# USB-Weather.net
KiCad netlist of a schematic drawn in EAGLE
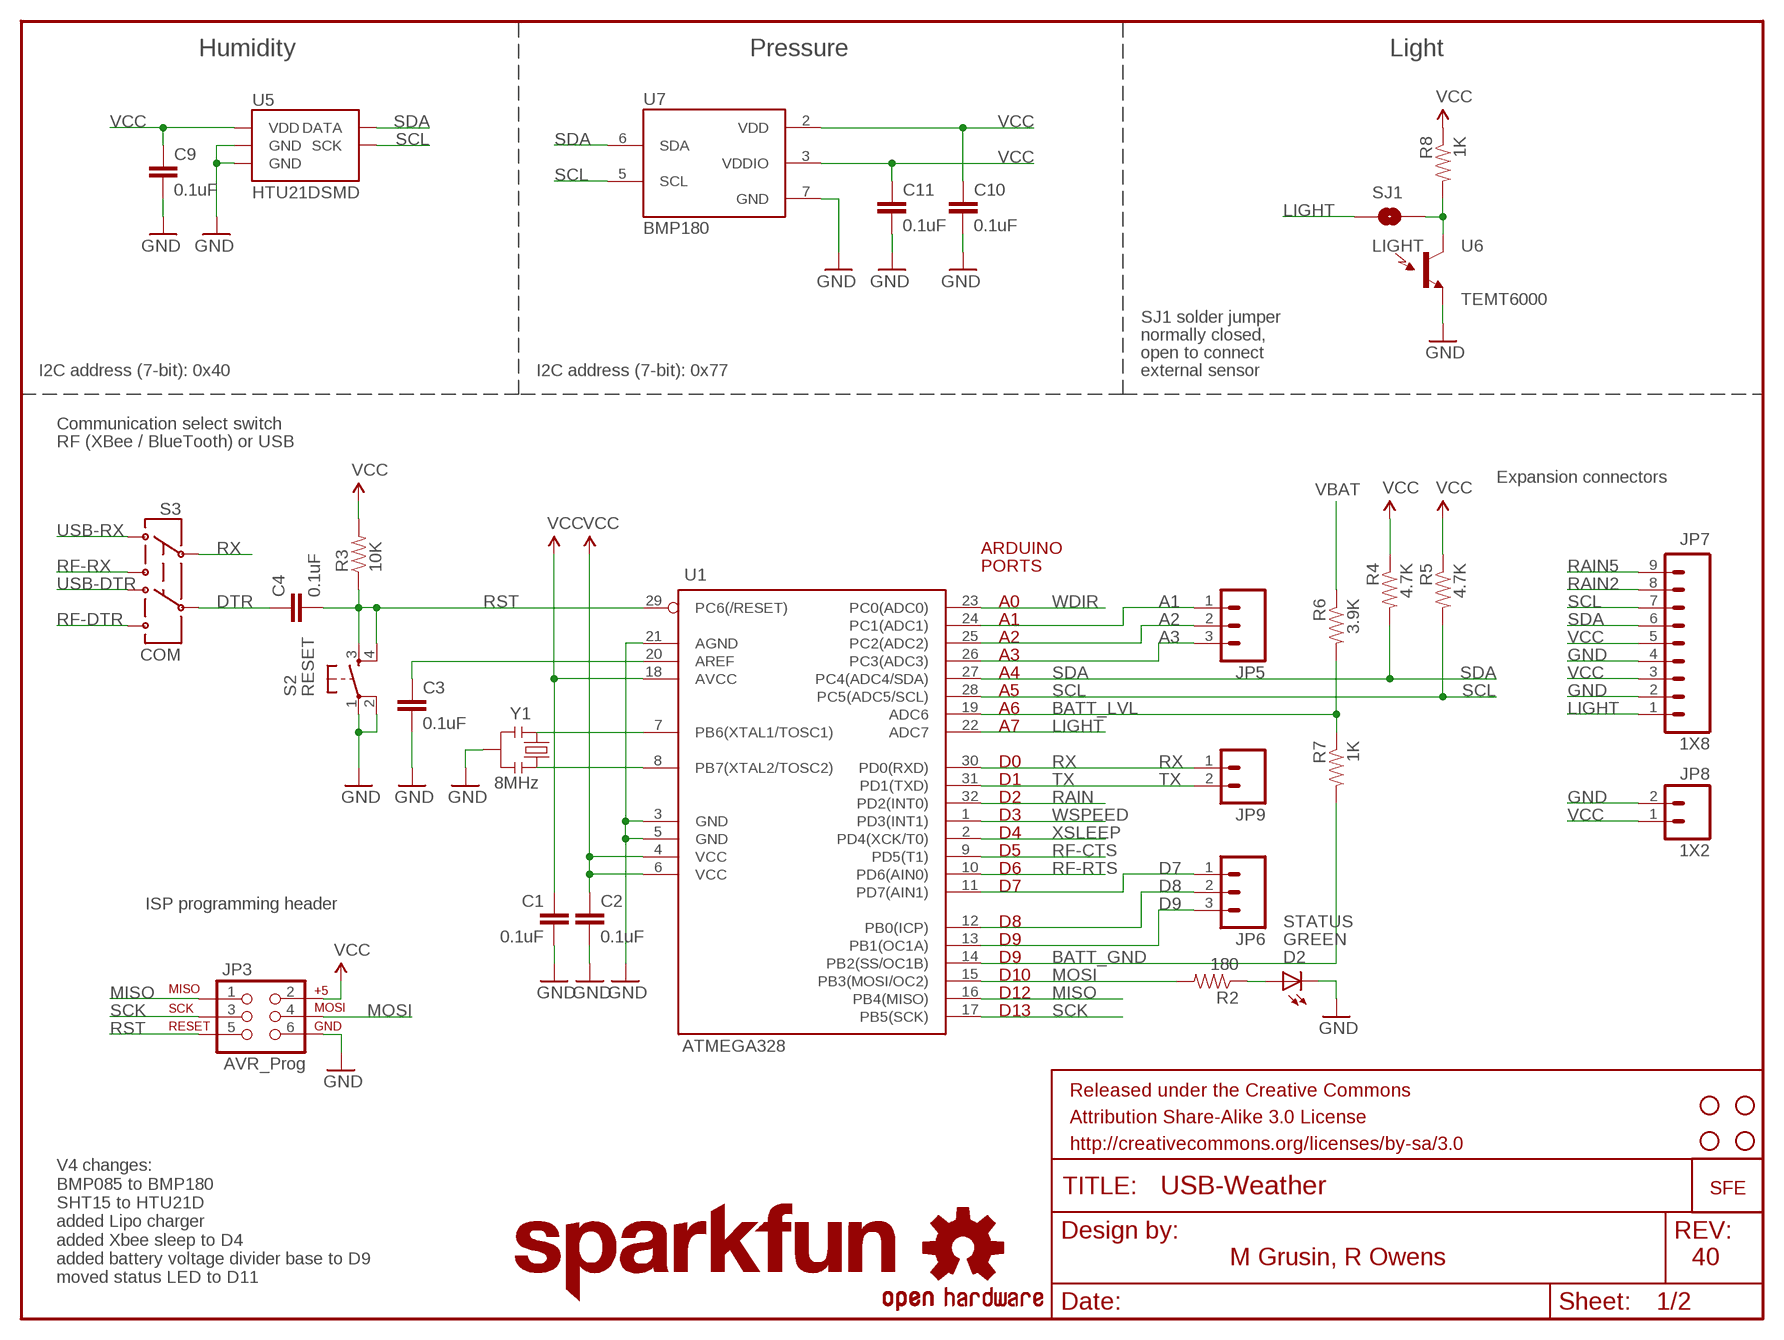
[diagram p0: schematic, sheet 1]
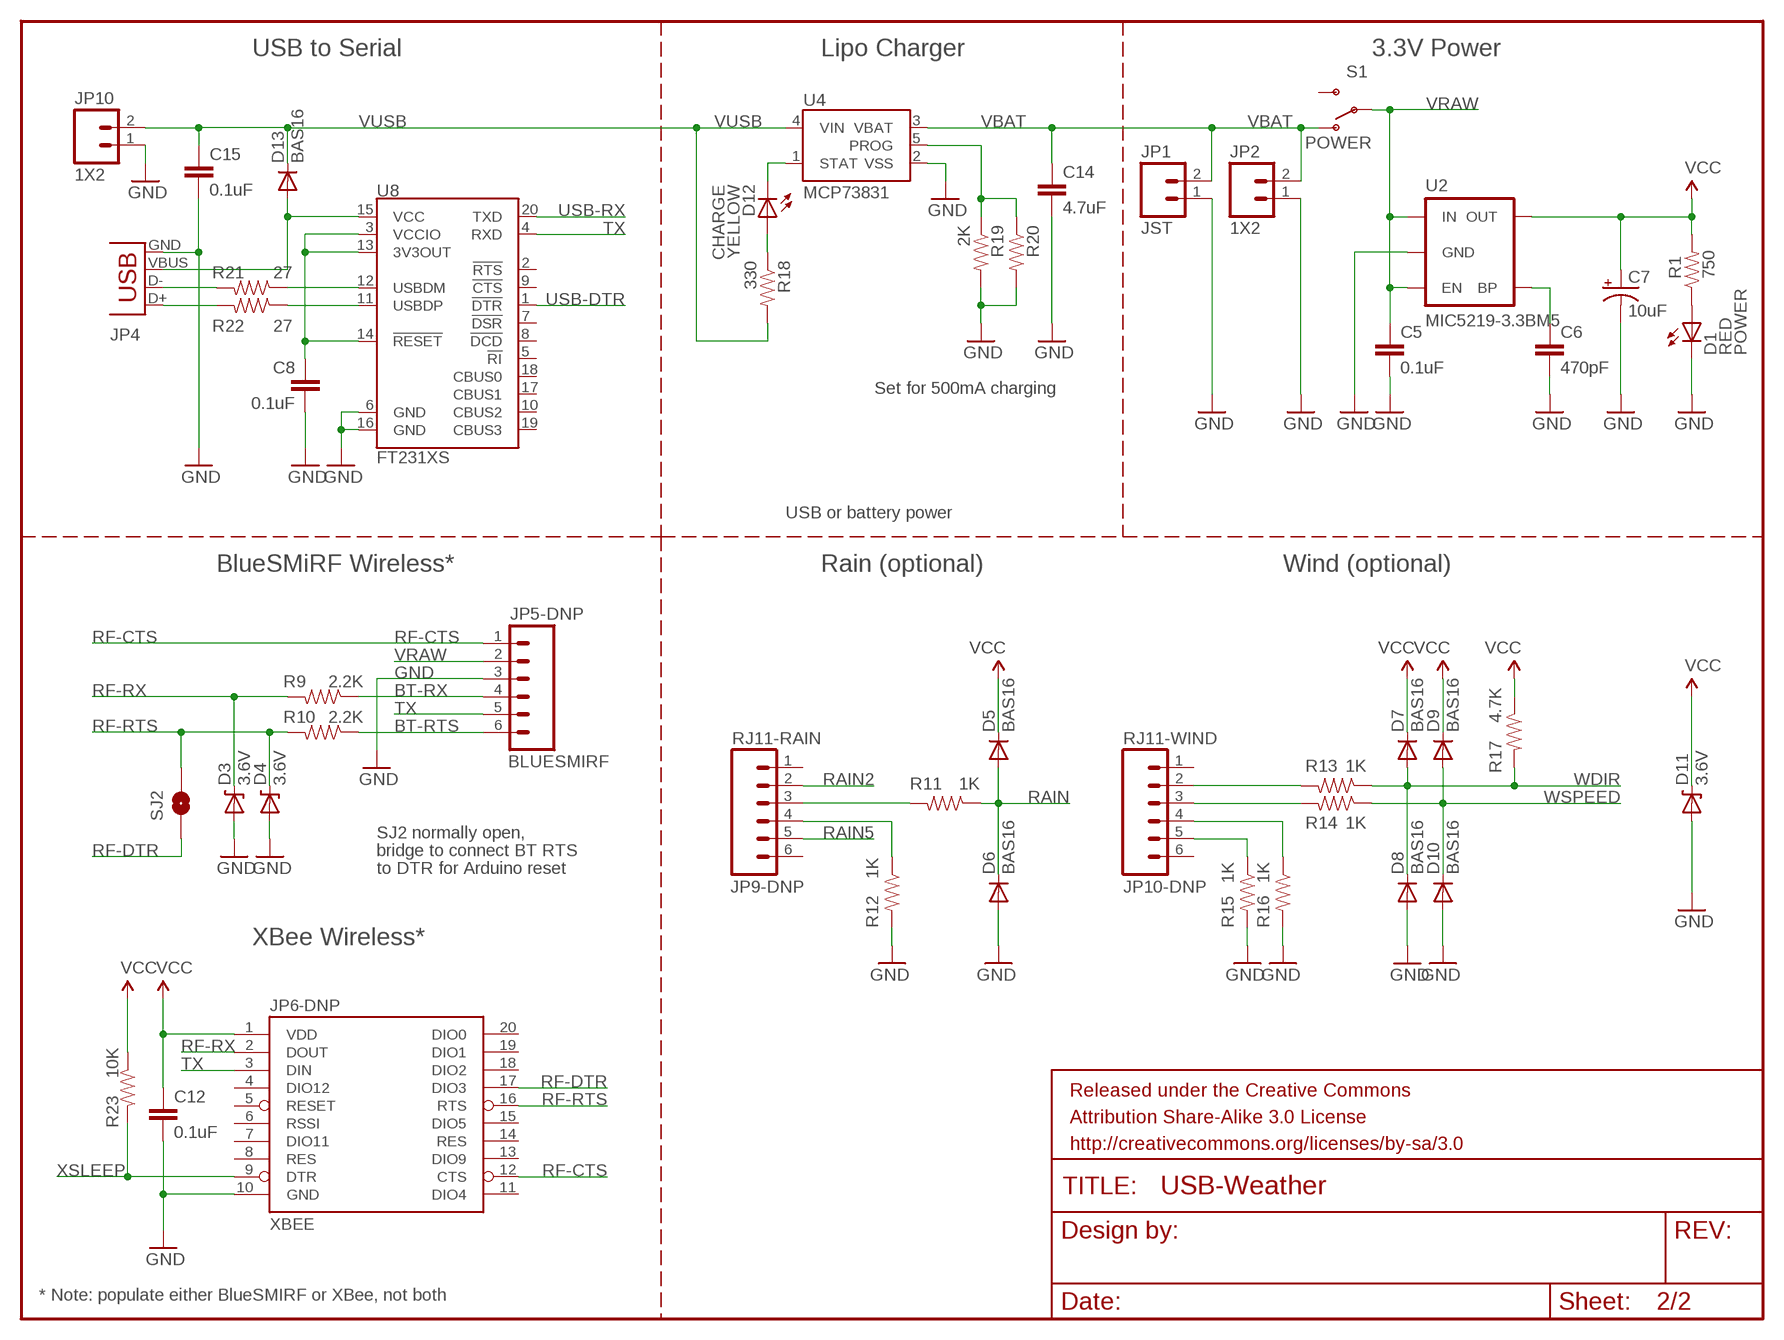
[diagram p1: schematic, sheet 2]

(export (version "E")
  (design (tool "Eeschema 10.0.6"))
  (components
    (comp (ref "C5")
      (value "0.1uF")
      (footprint "eagle-import:0603-CAP")
      (libsource (lib "eagle-import") (part "CAP0603-CAP"))
    )
    (comp (ref "C6")
      (value "470pF")
      (footprint "eagle-import:0603-CAP")
      (libsource (lib "eagle-import") (part "CAP0603-CAP"))
    )
    (comp (ref "C7")
      (value "10uF")
      (footprint "eagle-import:EIA3216")
      (libsource (lib "eagle-import") (part "CAP_POL1206"))
    )
    (comp (ref "C8")
      (value "0.1uF")
      (footprint "eagle-import:0603-CAP")
      (libsource (lib "eagle-import") (part "CAP0603-CAP"))
    )
    (comp (ref "C12")
      (value "0.1uF")
      (footprint "eagle-import:0603-CAP")
      (libsource (lib "eagle-import") (part "CAP0603-CAP"))
    )
    (comp (ref "C14")
      (value "4.7uF")
      (footprint "eagle-import:0603-CAP")
      (libsource (lib "eagle-import") (part "CAP0603-CAP"))
    )
    (comp (ref "C15")
      (value "0.1uF")
      (footprint "eagle-import:0603-CAP")
      (libsource (lib "eagle-import") (part "CAP0603-CAP"))
    )
    (comp (ref "D1")
      (value "RED")
      (footprint "eagle-import:LED-0603")
      (libsource (lib "eagle-import") (part "LED0603"))
    )
    (comp (ref "D3")
      (value "3.6V")
      (footprint "eagle-import:SOD-323")
      (libsource (lib "eagle-import") (part "DIODE-ZENER-BZT52"))
    )
    (comp (ref "D4")
      (value "3.6V")
      (footprint "eagle-import:SOD-323")
      (libsource (lib "eagle-import") (part "DIODE-ZENER-BZT52"))
    )
    (comp (ref "D5")
      (value "BAS16")
      (footprint "eagle-import:SOD-323")
      (libsource (lib "eagle-import") (part "DIODESOD"))
    )
    (comp (ref "D6")
      (value "BAS16")
      (footprint "eagle-import:SOD-323")
      (libsource (lib "eagle-import") (part "DIODESOD"))
    )
    (comp (ref "D7")
      (value "BAS16")
      (footprint "eagle-import:SOD-323")
      (libsource (lib "eagle-import") (part "DIODESOD"))
    )
    (comp (ref "D8")
      (value "BAS16")
      (footprint "eagle-import:SOD-323")
      (libsource (lib "eagle-import") (part "DIODESOD"))
    )
    (comp (ref "D9")
      (value "BAS16")
      (footprint "eagle-import:SOD-323")
      (libsource (lib "eagle-import") (part "DIODESOD"))
    )
    (comp (ref "D10")
      (value "BAS16")
      (footprint "eagle-import:SOD-323")
      (libsource (lib "eagle-import") (part "DIODESOD"))
    )
    (comp (ref "D11")
      (value "3.6V")
      (footprint "eagle-import:SOD-323")
      (libsource (lib "eagle-import") (part "DIODE-ZENER-BZT52"))
    )
    (comp (ref "D12")
      (value "YELLOW")
      (footprint "eagle-import:LED-0603")
      (libsource (lib "eagle-import") (part "LED0603"))
    )
    (comp (ref "D13")
      (value "BAS16")
      (footprint "eagle-import:SOD-323")
      (libsource (lib "eagle-import") (part "DIODESOD"))
    )
    (comp (ref "FRAME1")
      (value "FRAME-LETTER")
      (footprint "eagle-import:CREATIVE_COMMONS")
      (libsource (lib "eagle-import") (part "FRAME-LETTER"))
    )
    (comp (ref "JP1")
      (value "JST")
      (footprint "eagle-import:JST-2-SMD")
      (libsource (lib "eagle-import") (part "M02-JST-2MM-SMT"))
    )
    (comp (ref "JP2")
      (value "1X2")
      (footprint "eagle-import:1X02_NO_SILK")
      (libsource (lib "eagle-import") (part "M021X02_NO_SILK"))
    )
    (comp (ref "JP4")
      (value "USBSMD")
      (footprint "eagle-import:USB-MINIB")
      (libsource (lib "eagle-import") (part "USBSMD"))
    )
    (comp (ref "JP5-DNP")
      (value "BLUESMIRF")
      (footprint "eagle-import:1X06")
      (libsource (lib "eagle-import") (part "M06SIP"))
    )
    (comp (ref "JP6-DNP")
      (value "XBEE")
      (footprint "eagle-import:XBEE-1")
      (libsource (lib "eagle-import") (part "XBEE-1B1"))
    )
    (comp (ref "JP9-DNP")
      (value "RJ11-RAIN")
      (footprint "eagle-import:RJ11-6")
      (libsource (lib "eagle-import") (part "RJ11-6PTH"))
    )
    (comp (ref "JP10")
      (value "1X2")
      (footprint "eagle-import:1X02_NO_SILK")
      (libsource (lib "eagle-import") (part "M021X02_NO_SILK"))
    )
    (comp (ref "JP10-DNP")
      (value "RJ11-WIND")
      (footprint "eagle-import:RJ11-6")
      (libsource (lib "eagle-import") (part "RJ11-6PTH"))
    )
    (comp (ref "R1")
      (value "750")
      (footprint "eagle-import:0603-RES")
      (libsource (lib "eagle-import") (part "RESISTOR0603-RES"))
    )
    (comp (ref "R9")
      (value "2.2K")
      (footprint "eagle-import:0603-RES")
      (libsource (lib "eagle-import") (part "RESISTOR0603-RES"))
    )
    (comp (ref "R10")
      (value "2.2K")
      (footprint "eagle-import:0603-RES")
      (libsource (lib "eagle-import") (part "RESISTOR0603-RES"))
    )
    (comp (ref "R11")
      (value "1K")
      (footprint "eagle-import:0603-RES")
      (libsource (lib "eagle-import") (part "RESISTOR0603-RES"))
    )
    (comp (ref "R12")
      (value "1K")
      (footprint "eagle-import:0603-RES")
      (libsource (lib "eagle-import") (part "RESISTOR0603-RES"))
    )
    (comp (ref "R13")
      (value "1K")
      (footprint "eagle-import:0603-RES")
      (libsource (lib "eagle-import") (part "RESISTOR0603-RES"))
    )
    (comp (ref "R14")
      (value "1K")
      (footprint "eagle-import:0603-RES")
      (libsource (lib "eagle-import") (part "RESISTOR0603-RES"))
    )
    (comp (ref "R15")
      (value "1K")
      (footprint "eagle-import:0603-RES")
      (libsource (lib "eagle-import") (part "RESISTOR0603-RES"))
    )
    (comp (ref "R16")
      (value "1K")
      (footprint "eagle-import:0603-RES")
      (libsource (lib "eagle-import") (part "RESISTOR0603-RES"))
    )
    (comp (ref "R17")
      (value "4.7K")
      (footprint "eagle-import:0603-RES")
      (libsource (lib "eagle-import") (part "RESISTOR0603-RES"))
    )
    (comp (ref "R18")
      (value "330")
      (footprint "eagle-import:0603-RES")
      (libsource (lib "eagle-import") (part "RESISTOR0603-RES"))
    )
    (comp (ref "R19")
      (value "2K")
      (footprint "eagle-import:0603-RES")
      (libsource (lib "eagle-import") (part "RESISTOR0603-RES"))
    )
    (comp (ref "R20")
      (value "RESISTORPTH-1/6W")
      (footprint "eagle-import:1_6W-RES")
      (libsource (lib "eagle-import") (part "RESISTORPTH-1/6W"))
    )
    (comp (ref "R21")
      (value "27")
      (footprint "eagle-import:0603-RES")
      (libsource (lib "eagle-import") (part "RESISTOR0603-RES"))
    )
    (comp (ref "R22")
      (value "27")
      (footprint "eagle-import:0603-RES")
      (libsource (lib "eagle-import") (part "RESISTOR0603-RES"))
    )
    (comp (ref "R23")
      (value "10K")
      (footprint "eagle-import:0603-RES")
      (libsource (lib "eagle-import") (part "RESISTOR0603-RES"))
    )
    (comp (ref "S1")
      (value "POWER")
      (footprint "eagle-import:AYZ0202")
      (libsource (lib "eagle-import") (part "SWITCH-SPSTSMD"))
    )
    (comp (ref "SJ2")
      (value "SOLDERJUMPERNO")
      (footprint "eagle-import:SJ_2S-NO")
      (libsource (lib "eagle-import") (part "SOLDERJUMPERNO"))
    )
    (comp (ref "U2")
      (value "MIC5219-3.3BM5")
      (footprint "eagle-import:SOT23-5")
      (libsource (lib "eagle-import") (part "V_REG_LDOSMD"))
    )
    (comp (ref "U4")
      (value "MCP73831")
      (footprint "eagle-import:SOT23-5")
      (libsource (lib "eagle-import") (part "MCP73831"))
    )
    (comp (ref "U8")
      (value "FT231XS")
      (footprint "eagle-import:SSOP20_L")
      (libsource (lib "eagle-import") (part "FT231XS"))
    )
    (comp (ref "C1")
      (value "0.1uF")
      (footprint "eagle-import:0603-CAP")
      (libsource (lib "eagle-import") (part "CAP0603-CAP"))
    )
    (comp (ref "C2")
      (value "0.1uF")
      (footprint "eagle-import:0603-CAP")
      (libsource (lib "eagle-import") (part "CAP0603-CAP"))
    )
    (comp (ref "C3")
      (value "0.1uF")
      (footprint "eagle-import:0603-CAP")
      (libsource (lib "eagle-import") (part "CAP0603-CAP"))
    )
    (comp (ref "C4")
      (value "0.1uF")
      (footprint "eagle-import:0603-CAP")
      (libsource (lib "eagle-import") (part "CAP0603-CAP"))
    )
    (comp (ref "C9")
      (value "0.1uF")
      (footprint "eagle-import:0603-CAP")
      (libsource (lib "eagle-import") (part "CAP0603-CAP"))
    )
    (comp (ref "C10")
      (value "0.1uF")
      (footprint "eagle-import:0603-CAP")
      (libsource (lib "eagle-import") (part "CAP0603-CAP"))
    )
    (comp (ref "C11")
      (value "0.1uF")
      (footprint "eagle-import:0603-CAP")
      (libsource (lib "eagle-import") (part "CAP0603-CAP"))
    )
    (comp (ref "D2")
      (value "GREEN")
      (footprint "eagle-import:LED-0603")
      (libsource (lib "eagle-import") (part "LED0603"))
    )
    (comp (ref "FRAME3")
      (value "FRAME-LETTER")
      (footprint "eagle-import:CREATIVE_COMMONS")
      (libsource (lib "eagle-import") (part "FRAME-LETTER"))
    )
    (comp (ref "JP3")
      (value "AVR_Prog")
      (footprint "eagle-import:2X3")
      (libsource (lib "eagle-import") (part "AVR_SPI_PRG_6PTH"))
    )
    (comp (ref "JP5")
      (value "M03_ROUND_ONLY_NO_SILK")
      (footprint "eagle-import:1X03_ROUND_ONLY_NO_SILK")
      (libsource (lib "eagle-import") (part "M03_ROUND_ONLY_NO_SILK"))
    )
    (comp (ref "JP6")
      (value "M03_ROUND_ONLY_NO_SILK")
      (footprint "eagle-import:1X03_ROUND_ONLY_NO_SILK")
      (libsource (lib "eagle-import") (part "M03_ROUND_ONLY_NO_SILK"))
    )
    (comp (ref "JP7")
      (value "1X8")
      (footprint "eagle-import:1X09")
      (libsource (lib "eagle-import") (part "M09"))
    )
    (comp (ref "JP8")
      (value "1X2")
      (footprint "eagle-import:1X02_NO_SILK")
      (libsource (lib "eagle-import") (part "mike-temp_M021X02_NO_SILK"))
    )
    (comp (ref "JP9")
      (value "M021X02_NO_SILK")
      (footprint "eagle-import:1X02_NO_SILK")
      (libsource (lib "eagle-import") (part "mike-temp_M021X02_NO_SILK"))
    )
    (comp (ref "LOGO1")
      (value "LOGO-SFENEW")
      (footprint "eagle-import:SFE-NEW-WEBLOGO")
      (libsource (lib "eagle-import") (part "LOGO-SFENEW"))
    )
    (comp (ref "LOGO2")
      (value "OSHW-LOGOS")
      (footprint "eagle-import:OSHW-LOGO-S")
      (libsource (lib "eagle-import") (part "OSHW-LOGOS"))
    )
    (comp (ref "LOGO3")
      (value "SFE_LOGO_NAME.1_INCH")
      (footprint "eagle-import:SFE_LOGO_NAME_.1")
      (libsource (lib "eagle-import") (part "SFE_LOGO_NAME.1_INCH"))
    )
    (comp (ref "R2")
      (value "180")
      (footprint "eagle-import:0603-RES")
      (libsource (lib "eagle-import") (part "RESISTOR0603-RES"))
    )
    (comp (ref "R3")
      (value "10K")
      (footprint "eagle-import:0603-RES")
      (libsource (lib "eagle-import") (part "RESISTOR0603-RES"))
    )
    (comp (ref "R4")
      (value "4.7K")
      (footprint "eagle-import:0603-RES")
      (libsource (lib "eagle-import") (part "RESISTOR0603-RES"))
    )
    (comp (ref "R5")
      (value "4.7K")
      (footprint "eagle-import:0603-RES")
      (libsource (lib "eagle-import") (part "RESISTOR0603-RES"))
    )
    (comp (ref "R6")
      (value "3.9K")
      (footprint "eagle-import:0603-RES")
      (libsource (lib "eagle-import") (part "RESISTOR0603-RES"))
    )
    (comp (ref "R7")
      (value "1K")
      (footprint "eagle-import:0603-RES")
      (libsource (lib "eagle-import") (part "RESISTOR0603-RES"))
    )
    (comp (ref "R8")
      (value "1K")
      (footprint "eagle-import:0603-RES")
      (libsource (lib "eagle-import") (part "RESISTOR0603-RES"))
    )
    (comp (ref "S2")
      (value "RESET")
      (footprint "eagle-import:TACTILE_SWITCH_SMD")
      (libsource (lib "eagle-import") (part "TAC_SWITCHSMD"))
    )
    (comp (ref "S3")
      (value "COM")
      (footprint "eagle-import:AYZ0202")
      (libsource (lib "eagle-import") (part "SWITCH-DPDTSMD"))
    )
    (comp (ref "SJ1")
      (value "LIGHT")
      (footprint "eagle-import:SJ_2S")
      (libsource (lib "eagle-import") (part "SOLDERJUMPERNC"))
    )
    (comp (ref "U$2")
      (value "STAND-OFF")
      (footprint "eagle-import:STAND-OFF")
      (libsource (lib "eagle-import") (part "STAND-OFF"))
    )
    (comp (ref "U$3")
      (value "STAND-OFF")
      (footprint "eagle-import:STAND-OFF")
      (libsource (lib "eagle-import") (part "STAND-OFF"))
    )
    (comp (ref "U$4")
      (value "STAND-OFF")
      (footprint "eagle-import:STAND-OFF")
      (libsource (lib "eagle-import") (part "STAND-OFF"))
    )
    (comp (ref "U$5")
      (value "STAND-OFF")
      (footprint "eagle-import:STAND-OFF")
      (libsource (lib "eagle-import") (part "STAND-OFF"))
    )
    (comp (ref "U1")
      (value "ATMEGA328")
      (footprint "eagle-import:TQFP32-08")
      (libsource (lib "eagle-import") (part "AVR-MEGA8-AI"))
    )
    (comp (ref "U5")
      (value "HTU21DSMD")
      (footprint "eagle-import:HTU21D")
      (libsource (lib "eagle-import") (part "HTU21DSMD"))
    )
    (comp (ref "U6")
      (value "TEMT6000")
      (footprint "eagle-import:TEMT6000-SEN")
      (libsource (lib "eagle-import") (part "TEMT6000"))
    )
    (comp (ref "U7")
      (value "BMP180")
      (footprint "eagle-import:BMP180")
      (libsource (lib "eagle-import") (part "BMP180"))
    )
    (comp (ref "Y1")
      (value "8MHz")
      (footprint "eagle-import:RESONATOR-SMD")
      (libsource (lib "eagle-import") (part "RESONATORSMD"))
    )
  )
  (nets
    (net (code "1") (name "A1") (class "Default")
      (node (ref "JP5") (pin "1") (pinfunction "1_1") (pintype "passive"))
      (node (ref "U1") (pin "24") (pinfunction "PC1(ADC1)_24") (pintype "bidirectional"))
    )
    (net (code "2") (name "A2") (class "Default")
      (node (ref "JP5") (pin "2") (pinfunction "2_2") (pintype "passive"))
      (node (ref "U1") (pin "25") (pinfunction "PC2(ADC2)_25") (pintype "bidirectional"))
    )
    (net (code "3") (name "A3") (class "Default")
      (node (ref "JP5") (pin "3") (pinfunction "3_3") (pintype "passive"))
      (node (ref "U1") (pin "26") (pinfunction "PC3(ADC3)_26") (pintype "bidirectional"))
    )
    (net (code "4") (name "BATT_GND") (class "Default")
      (node (ref "R7") (pin "2") (pinfunction "2_2") (pintype "passive"))
      (node (ref "U1") (pin "14") (pinfunction "PB2(SS/OC1B)_14") (pintype "bidirectional"))
    )
    (net (code "5") (name "BATT_LVL") (class "Default")
      (node (ref "R6") (pin "2") (pinfunction "2_2") (pintype "passive"))
      (node (ref "R7") (pin "1") (pinfunction "1_1") (pintype "passive"))
      (node (ref "U1") (pin "19") (pinfunction "ADC6_19") (pintype "bidirectional"))
    )
    (net (code "6") (name "BT-RTS") (class "Default")
      (node (ref "JP5-DNP") (pin "6") (pinfunction "6_6") (pintype "passive"))
      (node (ref "R10") (pin "1") (pinfunction "1_1") (pintype "passive"))
    )
    (net (code "7") (name "BT-RX") (class "Default")
      (node (ref "JP5-DNP") (pin "4") (pinfunction "4_4") (pintype "passive"))
      (node (ref "R9") (pin "1") (pinfunction "1_1") (pintype "passive"))
    )
    (net (code "8") (name "D7") (class "Default")
      (node (ref "JP6") (pin "1") (pinfunction "1_1") (pintype "passive"))
      (node (ref "U1") (pin "11") (pinfunction "PD7(AIN1)_11") (pintype "bidirectional"))
    )
    (net (code "9") (name "D8") (class "Default")
      (node (ref "JP6") (pin "2") (pinfunction "2_2") (pintype "passive"))
      (node (ref "U1") (pin "12") (pinfunction "PB0(ICP)_12") (pintype "bidirectional"))
    )
    (net (code "10") (name "D9") (class "Default")
      (node (ref "JP6") (pin "3") (pinfunction "3_3") (pintype "passive"))
      (node (ref "U1") (pin "13") (pinfunction "PB1(OC1A)_13") (pintype "bidirectional"))
    )
    (net (code "11") (name "DTR") (class "Default")
      (node (ref "C4") (pin "1") (pinfunction "1_1") (pintype "passive"))
      (node (ref "S3") (pin "5") (pinfunction "5_5") (pintype "bidirectional"))
    )
    (net (code "12") (name "GND") (class "Default")
      (node (ref "C1") (pin "2") (pinfunction "2_2") (pintype "passive"))
      (node (ref "C10") (pin "2") (pinfunction "2_2") (pintype "passive"))
      (node (ref "C11") (pin "2") (pinfunction "2_2") (pintype "passive"))
      (node (ref "C12") (pin "2") (pinfunction "2_2") (pintype "passive"))
      (node (ref "C14") (pin "2") (pinfunction "2_2") (pintype "passive"))
      (node (ref "C15") (pin "2") (pinfunction "2_2") (pintype "passive"))
      (node (ref "C2") (pin "2") (pinfunction "2_2") (pintype "passive"))
      (node (ref "C3") (pin "2") (pinfunction "2_2") (pintype "passive"))
      (node (ref "C5") (pin "2") (pinfunction "2_2") (pintype "passive"))
      (node (ref "C6") (pin "2") (pinfunction "2_2") (pintype "passive"))
      (node (ref "C7") (pin "C") (pinfunction "-_C") (pintype "passive"))
      (node (ref "C8") (pin "2") (pinfunction "2_2") (pintype "passive"))
      (node (ref "C9") (pin "2") (pinfunction "2_2") (pintype "passive"))
      (node (ref "D1") (pin "C") (pinfunction "C_C") (pintype "passive"))
      (node (ref "D10") (pin "2") (pinfunction "A_2") (pintype "passive"))
      (node (ref "D11") (pin "2") (pinfunction "A_2") (pintype "passive"))
      (node (ref "D2") (pin "C") (pinfunction "C_C") (pintype "passive"))
      (node (ref "D3") (pin "2") (pinfunction "A_2") (pintype "passive"))
      (node (ref "D4") (pin "2") (pinfunction "A_2") (pintype "passive"))
      (node (ref "D6") (pin "2") (pinfunction "A_2") (pintype "passive"))
      (node (ref "D8") (pin "2") (pinfunction "A_2") (pintype "passive"))
      (node (ref "JP1") (pin "1") (pinfunction "1_1") (pintype "passive"))
      (node (ref "JP10") (pin "1") (pinfunction "1_1") (pintype "passive"))
      (node (ref "JP2") (pin "1") (pinfunction "1_1") (pintype "passive"))
      (node (ref "JP3") (pin "6") (pinfunction "6_6") (pintype "passive"))
      (node (ref "JP4") (pin "GND") (pinfunction "GND_GND") (pintype "bidirectional"))
      (node (ref "JP5-DNP") (pin "3") (pinfunction "3_3") (pintype "passive"))
      (node (ref "JP6-DNP") (pin "10") (pinfunction "GND_10") (pintype "power_in"))
      (node (ref "JP7") (pin "2") (pinfunction "2_2") (pintype "passive"))
      (node (ref "JP7") (pin "4") (pinfunction "4_4") (pintype "passive"))
      (node (ref "JP8") (pin "2") (pinfunction "2_2") (pintype "passive"))
      (node (ref "R12") (pin "2") (pinfunction "2_2") (pintype "passive"))
      (node (ref "R15") (pin "2") (pinfunction "2_2") (pintype "passive"))
      (node (ref "R16") (pin "2") (pinfunction "2_2") (pintype "passive"))
      (node (ref "R19") (pin "2") (pinfunction "2_2") (pintype "passive"))
      (node (ref "R20") (pin "2") (pinfunction "2_2") (pintype "passive"))
      (node (ref "S2") (pin "1") (pinfunction "1_1") (pintype "passive"))
      (node (ref "S2") (pin "2") (pinfunction "2_2") (pintype "passive"))
      (node (ref "U1") (pin "21") (pinfunction "AGND_21") (pintype "bidirectional"))
      (node (ref "U1") (pin "3") (pinfunction "GND_3") (pintype "bidirectional"))
      (node (ref "U1") (pin "5") (pinfunction "GND_5") (pintype "bidirectional"))
      (node (ref "U2") (pin "2") (pinfunction "GND_2") (pintype "input"))
      (node (ref "U4") (pin "2") (pinfunction "VSS_2") (pintype "power_in"))
      (node (ref "U5") (pin "7") (pinfunction "GND_7") (pintype "power_in"))
      (node (ref "U5") (pin "GND") (pinfunction "GND_GND") (pintype "power_in"))
      (node (ref "U6") (pin "EMITTER") (pinfunction "E1_EMITTER") (pintype "passive"))
      (node (ref "U7") (pin "7") (pinfunction "GND_7") (pintype "power_in"))
      (node (ref "U8") (pin "16") (pinfunction "GND_16") (pintype "bidirectional"))
      (node (ref "U8") (pin "6") (pinfunction "GND_6") (pintype "bidirectional"))
      (node (ref "Y1") (pin "2") (pinfunction "2_2") (pintype "passive"))
    )
    (net (code "13") (name "LIGHT") (class "Default")
      (node (ref "JP7") (pin "1") (pinfunction "1_1") (pintype "passive"))
      (node (ref "SJ1") (pin "1") (pinfunction "1_1") (pintype "passive"))
      (node (ref "U1") (pin "22") (pinfunction "ADC7_22") (pintype "bidirectional"))
    )
    (net (code "14") (name "MISO") (class "Default")
      (node (ref "JP3") (pin "1") (pinfunction "1_1") (pintype "passive"))
      (node (ref "U1") (pin "16") (pinfunction "PB4(MISO)_16") (pintype "bidirectional"))
    )
    (net (code "15") (name "MOSI") (class "Default")
      (node (ref "JP3") (pin "4") (pinfunction "4_4") (pintype "passive"))
      (node (ref "R2") (pin "2") (pinfunction "2_2") (pintype "passive"))
      (node (ref "U1") (pin "15") (pinfunction "PB3(MOSI/OC2)_15") (pintype "bidirectional"))
    )
    (net (code "16") (name "Net-(D1-PadA)") (class "Default")
      (node (ref "D1") (pin "A") (pinfunction "A_A") (pintype "passive"))
      (node (ref "R1") (pin "1") (pinfunction "1_1") (pintype "passive"))
    )
    (net (code "17") (name "Net-(D2-PadA)") (class "Default")
      (node (ref "D2") (pin "A") (pinfunction "A_A") (pintype "passive"))
      (node (ref "R2") (pin "1") (pinfunction "1_1") (pintype "passive"))
    )
    (net (code "18") (name "Net-(D12-PadA)") (class "Default")
      (node (ref "D12") (pin "A") (pinfunction "A_A") (pintype "passive"))
      (node (ref "R18") (pin "1") (pinfunction "1_1") (pintype "passive"))
    )
    (net (code "19") (name "Net-(D13-A)") (class "Default")
      (node (ref "D13") (pin "2") (pinfunction "A_2") (pintype "passive"))
      (node (ref "JP4") (pin "VBUS") (pinfunction "VBUS_VBUS") (pintype "bidirectional"))
      (node (ref "U8") (pin "15") (pinfunction "VCC_15") (pintype "bidirectional"))
    )
    (net (code "20") (name "Net-(JP4-PadD+)") (class "Default")
      (node (ref "JP4") (pin "D+") (pinfunction "D+_D+") (pintype "bidirectional"))
      (node (ref "R22") (pin "2") (pinfunction "2_2") (pintype "passive"))
    )
    (net (code "21") (name "Net-(JP4-PadD-)") (class "Default")
      (node (ref "JP4") (pin "D-") (pinfunction "D-_D-") (pintype "bidirectional"))
      (node (ref "R21") (pin "2") (pinfunction "2_2") (pintype "passive"))
    )
    (net (code "22") (name "Net-(JP9-DNP-Pad3)") (class "Default")
      (node (ref "JP9-DNP") (pin "3") (pinfunction "3_3") (pintype "passive"))
      (node (ref "R11") (pin "2") (pinfunction "2_2") (pintype "passive"))
    )
    (net (code "23") (name "Net-(JP9-DNP-Pad4)") (class "Default")
      (node (ref "JP9-DNP") (pin "4") (pinfunction "4_4") (pintype "passive"))
      (node (ref "R12") (pin "1") (pinfunction "1_1") (pintype "passive"))
    )
    (net (code "24") (name "Net-(JP10-DNP-Pad2)") (class "Default")
      (node (ref "JP10-DNP") (pin "2") (pinfunction "2_2") (pintype "passive"))
      (node (ref "R13") (pin "2") (pinfunction "2_2") (pintype "passive"))
    )
    (net (code "25") (name "Net-(JP10-DNP-Pad3)") (class "Default")
      (node (ref "JP10-DNP") (pin "3") (pinfunction "3_3") (pintype "passive"))
      (node (ref "R14") (pin "2") (pinfunction "2_2") (pintype "passive"))
    )
    (net (code "26") (name "Net-(JP10-DNP-Pad4)") (class "Default")
      (node (ref "JP10-DNP") (pin "4") (pinfunction "4_4") (pintype "passive"))
      (node (ref "R16") (pin "1") (pinfunction "1_1") (pintype "passive"))
    )
    (net (code "27") (name "Net-(JP10-DNP-Pad5)") (class "Default")
      (node (ref "JP10-DNP") (pin "5") (pinfunction "5_5") (pintype "passive"))
      (node (ref "R15") (pin "1") (pinfunction "1_1") (pintype "passive"))
    )
    (net (code "28") (name "Net-(U1-AREF)") (class "Default")
      (node (ref "C3") (pin "1") (pinfunction "1_1") (pintype "passive"))
      (node (ref "U1") (pin "20") (pinfunction "AREF_20") (pintype "bidirectional"))
    )
    (net (code "29") (name "Net-(U1-PB6(XTAL1{slash}TOSC1))") (class "Default")
      (node (ref "U1") (pin "7") (pinfunction "PB6(XTAL1/TOSC1)_7") (pintype "bidirectional"))
      (node (ref "Y1") (pin "1") (pinfunction "1_1") (pintype "passive"))
    )
    (net (code "30") (name "Net-(U1-PB7(XTAL2{slash}TOSC2))") (class "Default")
      (node (ref "U1") (pin "8") (pinfunction "PB7(XTAL2/TOSC2)_8") (pintype "bidirectional"))
      (node (ref "Y1") (pin "3") (pinfunction "3_3") (pintype "passive"))
    )
    (net (code "31") (name "Net-(U2-BP)") (class "Default")
      (node (ref "C6") (pin "1") (pinfunction "1_1") (pintype "passive"))
      (node (ref "U2") (pin "4") (pinfunction "BP_4") (pintype "input"))
    )
    (net (code "32") (name "Net-(U4-PROG)") (class "Default")
      (node (ref "R19") (pin "1") (pinfunction "1_1") (pintype "passive"))
      (node (ref "R20") (pin "1") (pinfunction "1_1") (pintype "passive"))
      (node (ref "U4") (pin "5") (pinfunction "PROG_5") (pintype "input"))
    )
    (net (code "33") (name "Net-(U4-STAT)") (class "Default")
      (node (ref "D12") (pin "C") (pinfunction "C_C") (pintype "passive"))
      (node (ref "U4") (pin "1") (pinfunction "STAT_1") (pintype "output"))
    )
    (net (code "34") (name "Net-(U6-C1)") (class "Default")
      (node (ref "R8") (pin "2") (pinfunction "2_2") (pintype "passive"))
      (node (ref "SJ1") (pin "2") (pinfunction "2_2") (pintype "passive"))
      (node (ref "U6") (pin "COLLECTOR") (pinfunction "C1_COLLECTOR") (pintype "passive"))
    )
    (net (code "35") (name "Net-(U8-3V3OUT)") (class "Default")
      (node (ref "C8") (pin "1") (pinfunction "1_1") (pintype "passive"))
      (node (ref "U8") (pin "13") (pinfunction "3V3OUT_13") (pintype "bidirectional"))
      (node (ref "U8") (pin "14") (pinfunction "~{RESET}_14") (pintype "bidirectional"))
      (node (ref "U8") (pin "3") (pinfunction "VCCIO_3") (pintype "bidirectional"))
    )
    (net (code "36") (name "Net-(U8-USBDM)") (class "Default")
      (node (ref "R21") (pin "1") (pinfunction "1_1") (pintype "passive"))
      (node (ref "U8") (pin "12") (pinfunction "USBDM_12") (pintype "bidirectional"))
    )
    (net (code "37") (name "Net-(U8-USBDP)") (class "Default")
      (node (ref "R22") (pin "1") (pinfunction "1_1") (pintype "passive"))
      (node (ref "U8") (pin "11") (pinfunction "USBDP_11") (pintype "bidirectional"))
    )
    (net (code "38") (name "RAIN") (class "Default")
      (node (ref "D5") (pin "2") (pinfunction "A_2") (pintype "passive"))
      (node (ref "D6") (pin "1") (pinfunction "C_1") (pintype "passive"))
      (node (ref "R11") (pin "1") (pinfunction "1_1") (pintype "passive"))
      (node (ref "U1") (pin "32") (pinfunction "PD2(INT0)_32") (pintype "bidirectional"))
    )
    (net (code "39") (name "RAIN2") (class "Default")
      (node (ref "JP7") (pin "8") (pinfunction "8_8") (pintype "passive"))
      (node (ref "JP9-DNP") (pin "2") (pinfunction "2_2") (pintype "passive"))
    )
    (net (code "40") (name "RAIN5") (class "Default")
      (node (ref "JP7") (pin "9") (pinfunction "9_9") (pintype "passive"))
      (node (ref "JP9-DNP") (pin "5") (pinfunction "5_5") (pintype "passive"))
    )
    (net (code "41") (name "RF-CTS") (class "Default")
      (node (ref "JP5-DNP") (pin "1") (pinfunction "1_1") (pintype "passive"))
      (node (ref "JP6-DNP") (pin "12") (pinfunction "CTS_12") (pintype "output"))
      (node (ref "U1") (pin "9") (pinfunction "PD5(T1)_9") (pintype "bidirectional"))
    )
    (net (code "42") (name "RF-DTR") (class "Default")
      (node (ref "JP6-DNP") (pin "17") (pinfunction "DIO3_17") (pintype "bidirectional"))
      (node (ref "S3") (pin "6") (pinfunction "6_6") (pintype "bidirectional"))
      (node (ref "SJ2") (pin "1") (pinfunction "1_1") (pintype "passive"))
    )
    (net (code "43") (name "RF-RTS") (class "Default")
      (node (ref "D4") (pin "1") (pinfunction "C_1") (pintype "passive"))
      (node (ref "JP6-DNP") (pin "16") (pinfunction "RTS_16") (pintype "input"))
      (node (ref "R10") (pin "2") (pinfunction "2_2") (pintype "passive"))
      (node (ref "SJ2") (pin "2") (pinfunction "2_2") (pintype "passive"))
      (node (ref "U1") (pin "10") (pinfunction "PD6(AIN0)_10") (pintype "bidirectional"))
    )
    (net (code "44") (name "RF-RX") (class "Default")
      (node (ref "D3") (pin "1") (pinfunction "C_1") (pintype "passive"))
      (node (ref "JP6-DNP") (pin "2") (pinfunction "DOUT_2") (pintype "output"))
      (node (ref "R9") (pin "2") (pinfunction "2_2") (pintype "passive"))
      (node (ref "S3") (pin "3") (pinfunction "3_3") (pintype "bidirectional"))
    )
    (net (code "45") (name "RST") (class "Default")
      (node (ref "C4") (pin "2") (pinfunction "2_2") (pintype "passive"))
      (node (ref "JP3") (pin "5") (pinfunction "5_5") (pintype "passive"))
      (node (ref "R3") (pin "1") (pinfunction "1_1") (pintype "passive"))
      (node (ref "S2") (pin "3") (pinfunction "3_3") (pintype "passive"))
      (node (ref "S2") (pin "4") (pinfunction "4_4") (pintype "passive"))
      (node (ref "U1") (pin "29") (pinfunction "PC6(/RESET)_29") (pintype "bidirectional"))
    )
    (net (code "46") (name "RX") (class "Default")
      (node (ref "JP9") (pin "1") (pinfunction "1_1") (pintype "passive"))
      (node (ref "S3") (pin "2") (pinfunction "2_2") (pintype "bidirectional"))
      (node (ref "U1") (pin "30") (pinfunction "PD0(RXD)_30") (pintype "bidirectional"))
    )
    (net (code "47") (name "SCK") (class "Default")
      (node (ref "JP3") (pin "3") (pinfunction "3_3") (pintype "passive"))
      (node (ref "U1") (pin "17") (pinfunction "PB5(SCK)_17") (pintype "bidirectional"))
    )
    (net (code "48") (name "SCL") (class "Default")
      (node (ref "JP7") (pin "7") (pinfunction "7_7") (pintype "passive"))
      (node (ref "R5") (pin "2") (pinfunction "2_2") (pintype "passive"))
      (node (ref "U1") (pin "28") (pinfunction "PC5(ADC5/SCL)_28") (pintype "bidirectional"))
      (node (ref "U5") (pin "SCK") (pinfunction "SCK_SCK") (pintype "input"))
      (node (ref "U7") (pin "5") (pinfunction "SCL_5") (pintype "input"))
    )
    (net (code "49") (name "SDA") (class "Default")
      (node (ref "JP7") (pin "6") (pinfunction "6_6") (pintype "passive"))
      (node (ref "R4") (pin "2") (pinfunction "2_2") (pintype "passive"))
      (node (ref "U1") (pin "27") (pinfunction "PC4(ADC4/SDA)_27") (pintype "bidirectional"))
      (node (ref "U5") (pin "DATA") (pinfunction "DATA_DATA") (pintype "bidirectional"))
      (node (ref "U7") (pin "6") (pinfunction "SDA_6") (pintype "bidirectional"))
    )
    (net (code "50") (name "TX") (class "Default")
      (node (ref "JP5-DNP") (pin "5") (pinfunction "5_5") (pintype "passive"))
      (node (ref "JP6-DNP") (pin "3") (pinfunction "DIN_3") (pintype "input"))
      (node (ref "JP9") (pin "2") (pinfunction "2_2") (pintype "passive"))
      (node (ref "U1") (pin "31") (pinfunction "PD1(TXD)_31") (pintype "bidirectional"))
      (node (ref "U8") (pin "4") (pinfunction "RXD_4") (pintype "bidirectional"))
    )
    (net (code "51") (name "USB-DTR") (class "Default")
      (node (ref "S3") (pin "4") (pinfunction "4_4") (pintype "bidirectional"))
      (node (ref "U8") (pin "1") (pinfunction "~{DTR}_1") (pintype "bidirectional"))
    )
    (net (code "52") (name "USB-RX") (class "Default")
      (node (ref "S3") (pin "1") (pinfunction "1_1") (pintype "bidirectional"))
      (node (ref "U8") (pin "20") (pinfunction "TXD_20") (pintype "bidirectional"))
    )
    (net (code "53") (name "VBAT") (class "Default")
      (node (ref "C14") (pin "1") (pinfunction "1_1") (pintype "passive"))
      (node (ref "JP1") (pin "2") (pinfunction "2_2") (pintype "passive"))
      (node (ref "JP2") (pin "2") (pinfunction "2_2") (pintype "passive"))
      (node (ref "R6") (pin "1") (pinfunction "1_1") (pintype "passive"))
      (node (ref "S1") (pin "1") (pinfunction "O_1") (pintype "passive"))
      (node (ref "U4") (pin "3") (pinfunction "VBAT_3") (pintype "power_in"))
    )
    (net (code "54") (name "VCC") (class "Default")
      (node (ref "C1") (pin "1") (pinfunction "1_1") (pintype "passive"))
      (node (ref "C10") (pin "1") (pinfunction "1_1") (pintype "passive"))
      (node (ref "C11") (pin "1") (pinfunction "1_1") (pintype "passive"))
      (node (ref "C12") (pin "1") (pinfunction "1_1") (pintype "passive"))
      (node (ref "C2") (pin "1") (pinfunction "1_1") (pintype "passive"))
      (node (ref "C7") (pin "A") (pinfunction "+_A") (pintype "passive"))
      (node (ref "C9") (pin "1") (pinfunction "1_1") (pintype "passive"))
      (node (ref "D11") (pin "1") (pinfunction "C_1") (pintype "passive"))
      (node (ref "D5") (pin "1") (pinfunction "C_1") (pintype "passive"))
      (node (ref "D7") (pin "1") (pinfunction "C_1") (pintype "passive"))
      (node (ref "D9") (pin "1") (pinfunction "C_1") (pintype "passive"))
      (node (ref "JP3") (pin "2") (pinfunction "2_2") (pintype "passive"))
      (node (ref "JP6-DNP") (pin "1") (pinfunction "VDD_1") (pintype "power_in"))
      (node (ref "JP7") (pin "3") (pinfunction "3_3") (pintype "passive"))
      (node (ref "JP7") (pin "5") (pinfunction "5_5") (pintype "passive"))
      (node (ref "JP8") (pin "1") (pinfunction "1_1") (pintype "passive"))
      (node (ref "R1") (pin "2") (pinfunction "2_2") (pintype "passive"))
      (node (ref "R17") (pin "1") (pinfunction "1_1") (pintype "passive"))
      (node (ref "R23") (pin "1") (pinfunction "1_1") (pintype "passive"))
      (node (ref "R3") (pin "2") (pinfunction "2_2") (pintype "passive"))
      (node (ref "R4") (pin "1") (pinfunction "1_1") (pintype "passive"))
      (node (ref "R5") (pin "1") (pinfunction "1_1") (pintype "passive"))
      (node (ref "R8") (pin "1") (pinfunction "1_1") (pintype "passive"))
      (node (ref "U1") (pin "18") (pinfunction "AVCC_18") (pintype "bidirectional"))
      (node (ref "U1") (pin "4") (pinfunction "VCC_4") (pintype "bidirectional"))
      (node (ref "U1") (pin "6") (pinfunction "VCC_6") (pintype "bidirectional"))
      (node (ref "U2") (pin "5") (pinfunction "OUT_5") (pintype "passive"))
      (node (ref "U5") (pin "VDD") (pinfunction "VDD_VDD") (pintype "power_in"))
      (node (ref "U7") (pin "2") (pinfunction "VDD_2") (pintype "power_in"))
      (node (ref "U7") (pin "3") (pinfunction "VDDIO_3") (pintype "power_in"))
    )
    (net (code "55") (name "VRAW") (class "Default")
      (node (ref "C5") (pin "1") (pinfunction "1_1") (pintype "passive"))
      (node (ref "JP5-DNP") (pin "2") (pinfunction "2_2") (pintype "passive"))
      (node (ref "S1") (pin "2") (pinfunction "P_2") (pintype "passive"))
      (node (ref "U2") (pin "1") (pinfunction "IN_1") (pintype "input"))
      (node (ref "U2") (pin "3") (pinfunction "EN_3") (pintype "input"))
    )
    (net (code "56") (name "VUSB") (class "Default")
      (node (ref "C15") (pin "1") (pinfunction "1_1") (pintype "passive"))
      (node (ref "D13") (pin "1") (pinfunction "C_1") (pintype "passive"))
      (node (ref "JP10") (pin "2") (pinfunction "2_2") (pintype "passive"))
      (node (ref "R18") (pin "2") (pinfunction "2_2") (pintype "passive"))
      (node (ref "U4") (pin "4") (pinfunction "VIN_4") (pintype "power_in"))
    )
    (net (code "57") (name "WDIR") (class "Default")
      (node (ref "D7") (pin "2") (pinfunction "A_2") (pintype "passive"))
      (node (ref "D8") (pin "1") (pinfunction "C_1") (pintype "passive"))
      (node (ref "R13") (pin "1") (pinfunction "1_1") (pintype "passive"))
      (node (ref "R17") (pin "2") (pinfunction "2_2") (pintype "passive"))
      (node (ref "U1") (pin "23") (pinfunction "PC0(ADC0)_23") (pintype "bidirectional"))
    )
    (net (code "58") (name "WSPEED") (class "Default")
      (node (ref "D10") (pin "1") (pinfunction "C_1") (pintype "passive"))
      (node (ref "D9") (pin "2") (pinfunction "A_2") (pintype "passive"))
      (node (ref "R14") (pin "1") (pinfunction "1_1") (pintype "passive"))
      (node (ref "U1") (pin "1") (pinfunction "PD3(INT1)_1") (pintype "bidirectional"))
    )
    (net (code "59") (name "XSLEEP") (class "Default")
      (node (ref "JP6-DNP") (pin "9") (pinfunction "DTR_9") (pintype "bidirectional"))
      (node (ref "R23") (pin "2") (pinfunction "2_2") (pintype "passive"))
      (node (ref "U1") (pin "2") (pinfunction "PD4(XCK/T0)_2") (pintype "bidirectional"))
    )
    (net (code "60") (name "unconnected-(JP6-DNP-DIO0-Pad20)") (class "Default")
      (node (ref "JP6-DNP") (pin "20") (pinfunction "DIO0_20") (pintype "bidirectional"))
    )
    (net (code "61") (name "unconnected-(JP6-DNP-DIO1-Pad19)") (class "Default")
      (node (ref "JP6-DNP") (pin "19") (pinfunction "DIO1_19") (pintype "bidirectional"))
    )
    (net (code "62") (name "unconnected-(JP6-DNP-DIO2-Pad18)") (class "Default")
      (node (ref "JP6-DNP") (pin "18") (pinfunction "DIO2_18") (pintype "bidirectional"))
    )
    (net (code "63") (name "unconnected-(JP6-DNP-DIO4-Pad11)") (class "Default")
      (node (ref "JP6-DNP") (pin "11") (pinfunction "DIO4_11") (pintype "bidirectional"))
    )
    (net (code "64") (name "unconnected-(JP6-DNP-DIO5-Pad15)") (class "Default")
      (node (ref "JP6-DNP") (pin "15") (pinfunction "DIO5_15") (pintype "bidirectional"))
    )
    (net (code "65") (name "unconnected-(JP6-DNP-DIO9-Pad13)") (class "Default")
      (node (ref "JP6-DNP") (pin "13") (pinfunction "DIO9_13") (pintype "bidirectional"))
    )
    (net (code "66") (name "unconnected-(JP6-DNP-DIO11-Pad7)") (class "Default")
      (node (ref "JP6-DNP") (pin "7") (pinfunction "DIO11_7") (pintype "bidirectional"))
    )
    (net (code "67") (name "unconnected-(JP6-DNP-DIO12-Pad4)") (class "Default")
      (node (ref "JP6-DNP") (pin "4") (pinfunction "DIO12_4") (pintype "bidirectional"))
    )
    (net (code "68") (name "unconnected-(JP6-DNP-RES-Pad8)") (class "Default")
      (node (ref "JP6-DNP") (pin "8") (pinfunction "RES_8") (pintype "bidirectional"))
    )
    (net (code "69") (name "unconnected-(JP6-DNP-RES-Pad14)") (class "Default")
      (node (ref "JP6-DNP") (pin "14") (pinfunction "RES_14") (pintype "bidirectional"))
    )
    (net (code "70") (name "unconnected-(JP6-DNP-RESET-Pad5)") (class "Default")
      (node (ref "JP6-DNP") (pin "5") (pinfunction "RESET_5") (pintype "input"))
    )
    (net (code "71") (name "unconnected-(JP6-DNP-RSSI-Pad6)") (class "Default")
      (node (ref "JP6-DNP") (pin "6") (pinfunction "RSSI_6") (pintype "bidirectional"))
    )
    (net (code "72") (name "unconnected-(JP9-DNP-Pad1)") (class "Default")
      (node (ref "JP9-DNP") (pin "1") (pinfunction "1_1") (pintype "passive"))
    )
    (net (code "73") (name "unconnected-(JP9-DNP-Pad6)") (class "Default")
      (node (ref "JP9-DNP") (pin "6") (pinfunction "6_6") (pintype "passive"))
    )
    (net (code "74") (name "unconnected-(JP10-DNP-Pad1)") (class "Default")
      (node (ref "JP10-DNP") (pin "1") (pinfunction "1_1") (pintype "passive"))
    )
    (net (code "75") (name "unconnected-(JP10-DNP-Pad6)") (class "Default")
      (node (ref "JP10-DNP") (pin "6") (pinfunction "6_6") (pintype "passive"))
    )
    (net (code "76") (name "unconnected-(S1-S-Pad3)") (class "Default")
      (node (ref "S1") (pin "3") (pinfunction "S_3") (pintype "passive"))
    )
    (net (code "77") (name "unconnected-(U8-CBUS0-Pad18)") (class "Default")
      (node (ref "U8") (pin "18") (pinfunction "CBUS0_18") (pintype "bidirectional"))
    )
    (net (code "78") (name "unconnected-(U8-CBUS1-Pad17)") (class "Default")
      (node (ref "U8") (pin "17") (pinfunction "CBUS1_17") (pintype "bidirectional"))
    )
    (net (code "79") (name "unconnected-(U8-CBUS2-Pad10)") (class "Default")
      (node (ref "U8") (pin "10") (pinfunction "CBUS2_10") (pintype "bidirectional"))
    )
    (net (code "80") (name "unconnected-(U8-CBUS3-Pad19)") (class "Default")
      (node (ref "U8") (pin "19") (pinfunction "CBUS3_19") (pintype "bidirectional"))
    )
    (net (code "81") (name "unconnected-(U8-~{CTS}-Pad9)") (class "Default")
      (node (ref "U8") (pin "9") (pinfunction "~{CTS}_9") (pintype "bidirectional"))
    )
    (net (code "82") (name "unconnected-(U8-~{DCD}-Pad8)") (class "Default")
      (node (ref "U8") (pin "8") (pinfunction "~{DCD}_8") (pintype "bidirectional"))
    )
    (net (code "83") (name "unconnected-(U8-~{DSR}-Pad7)") (class "Default")
      (node (ref "U8") (pin "7") (pinfunction "~{DSR}_7") (pintype "bidirectional"))
    )
    (net (code "84") (name "unconnected-(U8-~{RI}-Pad5)") (class "Default")
      (node (ref "U8") (pin "5") (pinfunction "~{RI}_5") (pintype "bidirectional"))
    )
    (net (code "85") (name "unconnected-(U8-~{RTS}-Pad2)") (class "Default")
      (node (ref "U8") (pin "2") (pinfunction "~{RTS}_2") (pintype "bidirectional"))
    )
  )
)
